# Sensor.net
KiCad netlist of a schematic drawn in Altium Designer
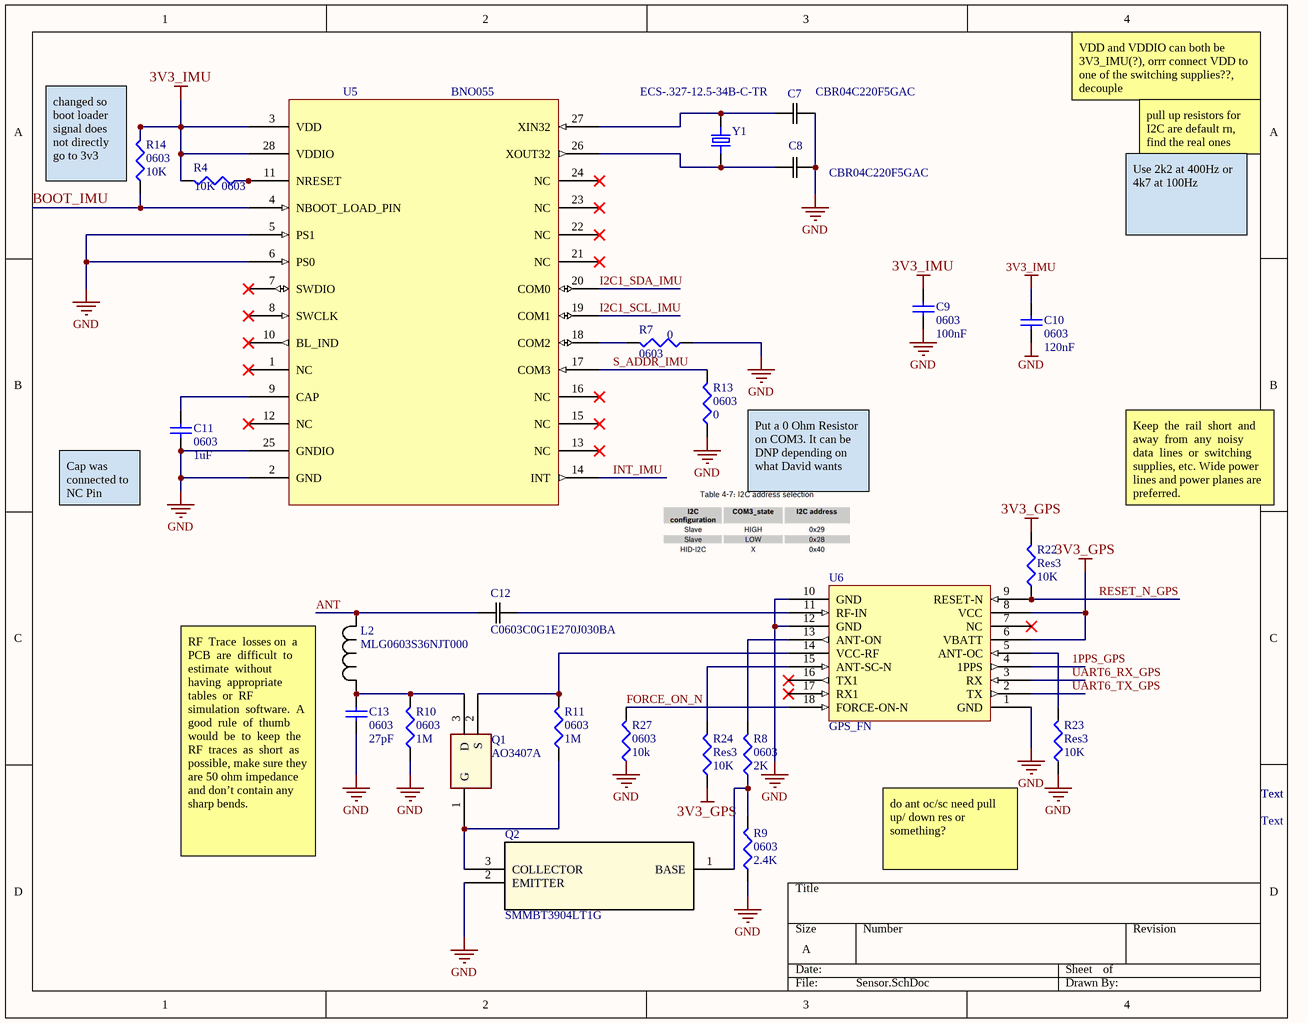
[diagram p0: Sensor.SchDoc]

(export (version "E")
  (design (tool "Eeschema 10.0.6"))
  (components
    (comp (ref "C7")
      (value "CBR04C220F5GAC")
      (footprint "swarm_crawler_pcb:CAPC10555_55N_KEM")
      (description "No Description Available")
      (fields (field (name "COPYRIGHT") "Copyright (C) 2023 Ultra Librarian. All rights reserved."))
      (libsource (lib "swarm_crawler_sch") (part "CBR04C220F5GAC"))
    )
    (comp (ref "C8")
      (value "CBR04C220F5GAC")
      (footprint "swarm_crawler_pcb:CAPC10555_55N_KEM")
      (description "No Description Available")
      (fields (field (name "COPYRIGHT") "Copyright (C) 2023 Ultra Librarian. All rights reserved."))
      (libsource (lib "swarm_crawler_sch") (part "CBR04C220F5GAC"))
    )
    (comp (ref "C9")
      (value "0603")
      (footprint "1608[0603]")
      (description "Capacitor (Semiconductor SIM Model)")
      (fields (field (name "ALTIUM_VALUE") "100nF") (field (name "PUBLISHER") "Altium Limited"))
      (libsource (lib "Miscellaneous Devices") (part "Cap Semi"))
    )
    (comp (ref "C10")
      (value "0603")
      (footprint "1608[0603]")
      (description "Capacitor (Semiconductor SIM Model)")
      (fields (field (name "ALTIUM_VALUE") "120nF") (field (name "PUBLISHER") "Altium Limited"))
      (libsource (lib "Miscellaneous Devices") (part "Cap Semi"))
    )
    (comp (ref "C11")
      (value "0603")
      (footprint "1608[0603]")
      (description "Capacitor (Semiconductor SIM Model)")
      (fields (field (name "ALTIUM_VALUE") "1uF") (field (name "PUBLISHER") "Altium Limited"))
      (libsource (lib "Miscellaneous Devices") (part "Cap Semi"))
    )
    (comp (ref "C12")
      (value "C0603C0G1E270J030BA")
      (footprint "swarm_crawler_pcb:CAP_0603_TDK")
      (description "No Description Available")
      (fields (field (name "COPYRIGHT") "Copyright (C) 2023 Ultra Librarian. All rights reserved."))
      (libsource (lib "swarm_crawler_sch") (part "C0603C0G1E270J030BA"))
    )
    (comp (ref "C13")
      (value "0603")
      (footprint "1608[0603]")
      (description "Capacitor (Semiconductor SIM Model)")
      (fields (field (name "ALTIUM_VALUE") "27pF") (field (name "PUBLISHER") "Altium Limited"))
      (libsource (lib "Miscellaneous Devices") (part "Cap Semi"))
    )
    (comp (ref "L2")
      (value "MLG0603S36NJT000")
      (footprint "swarm_crawler_pcb:IND_0603_TDK")
      (description "No Description Available")
      (fields (field (name "COPYRIGHT") "Copyright (C) 2023 Ultra Librarian. All rights reserved."))
      (libsource (lib "swarm_crawler_sch") (part "MLG0603S36NJT000"))
    )
    (comp (ref "Q1")
      (value "AO3407A")
      (footprint "swarm_crawler_pcb:SOT-23-3L_AOS")
      (description "No Description Available")
      (fields (field (name "COPYRIGHT") "Copyright (C) 2023 Ultra Librarian. All rights reserved."))
      (libsource (lib "swarm_crawler_sch") (part "AO3407A"))
    )
    (comp (ref "Q2")
      (value "SMMBT3904LT1G")
      (footprint "swarm_crawler_pcb:SOT-23-3_1P4X3P040_ONS")
      (description "No Description Available")
      (fields (field (name "COPYRIGHT") "Copyright (C) 2023 Ultra Librarian. All rights reserved."))
      (libsource (lib "swarm_crawler_sch") (part "SMMBT3904LT1G"))
    )
    (comp (ref "R4")
      (value "0603")
      (footprint "J1-0603")
      (description "Resistor")
      (fields (field (name "ALTIUM_VALUE") "10K") (field (name "PUBLISHER") "Altium Limited"))
      (libsource (lib "Miscellaneous Devices") (part "Res3"))
    )
    (comp (ref "R7")
      (value "0603")
      (footprint "J1-0603")
      (description "Resistor")
      (fields (field (name "ALTIUM_VALUE") "0") (field (name "PUBLISHER") "Altium Limited"))
      (libsource (lib "Miscellaneous Devices") (part "Res3"))
    )
    (comp (ref "R8")
      (value "0603")
      (footprint "J1-0603")
      (description "Resistor")
      (fields (field (name "ALTIUM_VALUE") "2K") (field (name "PUBLISHER") "Altium Limited"))
      (libsource (lib "Miscellaneous Devices") (part "Res3"))
    )
    (comp (ref "R9")
      (value "0603")
      (footprint "J1-0603")
      (description "Resistor")
      (fields (field (name "ALTIUM_VALUE") "2.4K") (field (name "PUBLISHER") "Altium Limited"))
      (libsource (lib "Miscellaneous Devices") (part "Res3"))
    )
    (comp (ref "R10")
      (value "0603")
      (footprint "J1-0603")
      (description "Resistor")
      (fields (field (name "ALTIUM_VALUE") "1M") (field (name "PUBLISHER") "Altium Limited"))
      (libsource (lib "Miscellaneous Devices") (part "Res3"))
    )
    (comp (ref "R11")
      (value "0603")
      (footprint "J1-0603")
      (description "Resistor")
      (fields (field (name "ALTIUM_VALUE") "1M") (field (name "PUBLISHER") "Altium Limited"))
      (libsource (lib "Miscellaneous Devices") (part "Res3"))
    )
    (comp (ref "R13")
      (value "0603")
      (footprint "J1-0603")
      (description "Resistor")
      (fields (field (name "ALTIUM_VALUE") "0") (field (name "PUBLISHER") "Altium Limited"))
      (libsource (lib "Miscellaneous Devices") (part "Res3"))
    )
    (comp (ref "R14")
      (value "0603")
      (footprint "J1-0603")
      (description "Resistor")
      (fields (field (name "ALTIUM_VALUE") "10K") (field (name "PUBLISHER") "Altium Limited"))
      (libsource (lib "Miscellaneous Devices") (part "Res3"))
    )
    (comp (ref "R22")
      (value "Res3")
      (footprint "J1-0603")
      (description "Resistor")
      (fields (field (name "ALTIUM_VALUE") "10K") (field (name "PUBLISHER") "Altium Limited"))
      (libsource (lib "Miscellaneous Devices") (part "Res3"))
    )
    (comp (ref "R23")
      (value "Res3")
      (footprint "J1-0603")
      (description "Resistor")
      (fields (field (name "ALTIUM_VALUE") "10K") (field (name "PUBLISHER") "Altium Limited"))
      (libsource (lib "Miscellaneous Devices") (part "Res3"))
    )
    (comp (ref "R24")
      (value "Res3")
      (footprint "J1-0603")
      (description "Resistor")
      (fields (field (name "ALTIUM_VALUE") "10K") (field (name "PUBLISHER") "Altium Limited"))
      (libsource (lib "Miscellaneous Devices") (part "Res3"))
    )
    (comp (ref "R27")
      (value "0603")
      (footprint "J1-0603")
      (description "Resistor")
      (fields (field (name "ALTIUM_VALUE") "10k") (field (name "PUBLISHER") "Altium Limited"))
      (libsource (lib "Miscellaneous Devices") (part "Res3"))
    )
    (comp (ref "U5")
      (value "BNO055")
      (footprint "swarm_crawler_pcb:QFN_BNO055_BOS")
      (description "No Description Available")
      (fields (field (name "COPYRIGHT") "Copyright (C) 2023 Ultra Librarian. All rights reserved."))
      (libsource (lib "swarm_crawler_sch") (part "BNO055"))
    )
    (comp (ref "U6")
      (value "GPS_FN")
      (footprint "swarm_crawler_pcb:SL871")
      (libsource (lib "swarm_crawler_sch") (part "GPS_FN"))
    )
    (comp (ref "Y1")
      (value "ECS-.327-12.5-34B-C-TR")
      (footprint "swarm_crawler_pcb:XTAL_ECS-.327-12.5-34B-C-TR")
      (description "32.768kHz Â±10ppm Crystal 12.5pF 70 kOhms 2-SMD, No Lead")
      (fields (field (name "DIGI-KEY_PART_NUMBER") "XC1968CT-ND") (field (name "MF") "ECS Inc."))
      (libsource (lib "swarm_crawler_sch") (part "ECS-.327-12.5-34B-C-TR"))
    )
  )
  (nets
    (net (code "1") (name "/1PPS_GPS") (class "Default")
      (node (ref "U6") (pin "4") (pinfunction "1PPS_4") (pintype "output"))
    )
    (net (code "2") (name "/ANT") (class "Default")
      (node (ref "C12") (pin "1") (pinfunction "1_1") (pintype "passive"))
      (node (ref "L2") (pin "1") (pinfunction "1_1") (pintype "passive"))
    )
    (net (code "3") (name "/BOOT_IMU") (class "Default")
      (node (ref "R14") (pin "1") (pinfunction "1_1") (pintype "passive"))
      (node (ref "U5") (pin "4") (pinfunction "NBOOT_LOAD_PIN_4") (pintype "input"))
    )
    (net (code "4") (name "/FORCE_ON_N") (class "Default")
      (node (ref "R27") (pin "2") (pinfunction "2_2") (pintype "passive"))
      (node (ref "U6") (pin "18") (pinfunction "FORCE-ON-N_18") (pintype "input"))
    )
    (net (code "5") (name "/I2C1_SCL_IMU") (class "Default")
      (node (ref "U5") (pin "19") (pinfunction "COM1_19") (pintype "bidirectional"))
    )
    (net (code "6") (name "/I2C1_SDA_IMU") (class "Default")
      (node (ref "U5") (pin "20") (pinfunction "COM0_20") (pintype "bidirectional"))
    )
    (net (code "7") (name "/INT_IMU") (class "Default")
      (node (ref "U5") (pin "14") (pinfunction "INT_14") (pintype "output"))
    )
    (net (code "8") (name "/RESET_N_GPS") (class "Default")
      (node (ref "R22") (pin "1") (pinfunction "1_1") (pintype "passive"))
      (node (ref "U6") (pin "9") (pinfunction "RESET-N_9") (pintype "input"))
    )
    (net (code "9") (name "/S_ADDR_IMU") (class "Default")
      (node (ref "R13") (pin "2") (pinfunction "2_2") (pintype "passive"))
      (node (ref "U5") (pin "17") (pinfunction "COM3_17") (pintype "input"))
    )
    (net (code "10") (name "/UART6_RX_GPS") (class "Default")
      (node (ref "U6") (pin "3") (pinfunction "RX_3") (pintype "input"))
    )
    (net (code "11") (name "/UART6_TX_GPS") (class "Default")
      (node (ref "U6") (pin "2") (pinfunction "TX_2") (pintype "output"))
    )
    (net (code "12") (name "3V3_GPS") (class "Default")
      (node (ref "R22") (pin "2") (pinfunction "2_2") (pintype "passive"))
      (node (ref "R24") (pin "1") (pinfunction "1_1") (pintype "passive"))
      (node (ref "U6") (pin "6") (pinfunction "VBATT_6") (pintype "power_in"))
      (node (ref "U6") (pin "8") (pinfunction "VCC_8") (pintype "power_in"))
    )
    (net (code "13") (name "3V3_IMU") (class "Default")
      (node (ref "C10") (pin "2") (pinfunction "2_2") (pintype "passive"))
      (node (ref "C9") (pin "2") (pinfunction "2_2") (pintype "passive"))
      (node (ref "R14") (pin "2") (pinfunction "2_2") (pintype "passive"))
      (node (ref "R4") (pin "2") (pinfunction "2_2") (pintype "passive"))
      (node (ref "U5") (pin "28") (pinfunction "VDDIO_28") (pintype "power_in"))
      (node (ref "U5") (pin "3") (pinfunction "VDD_3") (pintype "power_in"))
    )
    (net (code "14") (name "GND") (class "Default")
      (node (ref "C10") (pin "1") (pinfunction "1_1") (pintype "passive"))
      (node (ref "C11") (pin "1") (pinfunction "1_1") (pintype "passive"))
      (node (ref "C13") (pin "1") (pinfunction "1_1") (pintype "passive"))
      (node (ref "C7") (pin "2") (pinfunction "2_2") (pintype "passive"))
      (node (ref "C8") (pin "2") (pinfunction "2_2") (pintype "passive"))
      (node (ref "C9") (pin "1") (pinfunction "1_1") (pintype "passive"))
      (node (ref "Q2") (pin "2") (pinfunction "EMITTER_2") (pintype "passive"))
      (node (ref "R10") (pin "1") (pinfunction "1_1") (pintype "passive"))
      (node (ref "R13") (pin "1") (pinfunction "1_1") (pintype "passive"))
      (node (ref "R23") (pin "1") (pinfunction "1_1") (pintype "passive"))
      (node (ref "R7") (pin "1") (pinfunction "1_1") (pintype "passive"))
      (node (ref "R9") (pin "1") (pinfunction "1_1") (pintype "passive"))
      (node (ref "U5") (pin "2") (pinfunction "GND_2") (pintype "passive"))
      (node (ref "U5") (pin "25") (pinfunction "GNDIO_25") (pintype "passive"))
      (node (ref "U5") (pin "5") (pinfunction "PS1_5") (pintype "input"))
      (node (ref "U5") (pin "6") (pinfunction "PS0_6") (pintype "input"))
      (node (ref "U6") (pin "1") (pinfunction "GND_1") (pintype "power_in"))
      (node (ref "U6") (pin "10") (pinfunction "GND_10") (pintype "power_in"))
      (node (ref "U6") (pin "12") (pinfunction "GND_12") (pintype "power_in"))
    )
    (net (code "15") (name "Net-(Q1-D)") (class "Default")
      (node (ref "C13") (pin "2") (pinfunction "2_2") (pintype "passive"))
      (node (ref "L2") (pin "2") (pinfunction "2_2") (pintype "passive"))
      (node (ref "Q1") (pin "3") (pinfunction "D_3") (pintype "passive"))
      (node (ref "R10") (pin "2") (pinfunction "2_2") (pintype "passive"))
    )
    (net (code "16") (name "Net-(Q1-G)") (class "Default")
      (node (ref "Q1") (pin "1") (pinfunction "G_1") (pintype "passive"))
      (node (ref "Q2") (pin "3") (pinfunction "COLLECTOR_3") (pintype "passive"))
      (node (ref "R11") (pin "1") (pinfunction "1_1") (pintype "passive"))
    )
    (net (code "17") (name "Net-(Q1-S)") (class "Default")
      (node (ref "Q1") (pin "2") (pinfunction "S_2") (pintype "passive"))
      (node (ref "R11") (pin "2") (pinfunction "2_2") (pintype "passive"))
      (node (ref "U6") (pin "14") (pinfunction "VCC-RF_14") (pintype "power_in"))
    )
    (net (code "18") (name "Net-(Q2-BASE)") (class "Default")
      (node (ref "Q2") (pin "1") (pinfunction "BASE_1") (pintype "passive"))
      (node (ref "R8") (pin "1") (pinfunction "1_1") (pintype "passive"))
      (node (ref "R9") (pin "2") (pinfunction "2_2") (pintype "passive"))
    )
    (net (code "19") (name "Net-(U5-CAP)") (class "Default")
      (node (ref "C11") (pin "2") (pinfunction "2_2") (pintype "passive"))
      (node (ref "U5") (pin "9") (pinfunction "CAP_9") (pintype "passive"))
    )
    (net (code "20") (name "Net-(U5-COM2)") (class "Default")
      (node (ref "R7") (pin "2") (pinfunction "2_2") (pintype "passive"))
      (node (ref "U5") (pin "18") (pinfunction "COM2_18") (pintype "bidirectional"))
    )
    (net (code "21") (name "Net-(U5-NRESET)") (class "Default")
      (node (ref "R4") (pin "1") (pinfunction "1_1") (pintype "passive"))
      (node (ref "U5") (pin "11") (pinfunction "NRESET_11") (pintype "passive"))
    )
    (net (code "22") (name "Net-(U5-XIN32)") (class "Default")
      (node (ref "C7") (pin "1") (pinfunction "1_1") (pintype "passive"))
      (node (ref "U5") (pin "27") (pinfunction "XIN32_27") (pintype "input"))
      (node (ref "Y1") (pin "2") (pinfunction "2_2") (pintype "passive"))
    )
    (net (code "23") (name "Net-(U5-XOUT32)") (class "Default")
      (node (ref "C8") (pin "1") (pinfunction "1_1") (pintype "passive"))
      (node (ref "U5") (pin "26") (pinfunction "XOUT32_26") (pintype "output"))
      (node (ref "Y1") (pin "1") (pinfunction "1_1") (pintype "passive"))
    )
    (net (code "24") (name "Net-(U6-ANT-OC)") (class "Default")
      (node (ref "R23") (pin "2") (pinfunction "2_2") (pintype "passive"))
      (node (ref "U6") (pin "5") (pinfunction "ANT-OC_5") (pintype "input"))
    )
    (net (code "25") (name "Net-(U6-ANT-ON)") (class "Default")
      (node (ref "R8") (pin "2") (pinfunction "2_2") (pintype "passive"))
      (node (ref "U6") (pin "13") (pinfunction "ANT-ON_13") (pintype "output"))
    )
    (net (code "26") (name "Net-(U6-ANT-SC-N)") (class "Default")
      (node (ref "R24") (pin "2") (pinfunction "2_2") (pintype "passive"))
      (node (ref "U6") (pin "15") (pinfunction "ANT-SC-N_15") (pintype "input"))
    )
    (net (code "27") (name "Net-(U6-RF-IN)") (class "Default")
      (node (ref "C12") (pin "2") (pinfunction "2_2") (pintype "passive"))
      (node (ref "U6") (pin "11") (pinfunction "RF-IN_11") (pintype "input"))
    )
    (net (code "28") (name "unconnected-(R27-Pad1)") (class "Default")
      (node (ref "R27") (pin "1") (pinfunction "1_1") (pintype "passive"))
    )
    (net (code "29") (name "unconnected-(U5-BL_IND-Pad10)") (class "Default")
      (node (ref "U5") (pin "10") (pinfunction "BL_IND_10") (pintype "output+no_connect"))
    )
    (net (code "30") (name "unconnected-(U5-NC-Pad1)") (class "Default")
      (node (ref "U5") (pin "1") (pinfunction "NC_1") (pintype "passive+no_connect"))
    )
    (net (code "31") (name "unconnected-(U5-NC-Pad12)") (class "Default")
      (node (ref "U5") (pin "12") (pinfunction "NC_12") (pintype "passive+no_connect"))
    )
    (net (code "32") (name "unconnected-(U5-NC-Pad13)") (class "Default")
      (node (ref "U5") (pin "13") (pinfunction "NC_13") (pintype "passive+no_connect"))
    )
    (net (code "33") (name "unconnected-(U5-NC-Pad15)") (class "Default")
      (node (ref "U5") (pin "15") (pinfunction "NC_15") (pintype "passive+no_connect"))
    )
    (net (code "34") (name "unconnected-(U5-NC-Pad16)") (class "Default")
      (node (ref "U5") (pin "16") (pinfunction "NC_16") (pintype "passive+no_connect"))
    )
    (net (code "35") (name "unconnected-(U5-NC-Pad21)") (class "Default")
      (node (ref "U5") (pin "21") (pinfunction "NC_21") (pintype "passive+no_connect"))
    )
    (net (code "36") (name "unconnected-(U5-NC-Pad22)") (class "Default")
      (node (ref "U5") (pin "22") (pinfunction "NC_22") (pintype "passive+no_connect"))
    )
    (net (code "37") (name "unconnected-(U5-NC-Pad23)") (class "Default")
      (node (ref "U5") (pin "23") (pinfunction "NC_23") (pintype "passive+no_connect"))
    )
    (net (code "38") (name "unconnected-(U5-NC-Pad24)") (class "Default")
      (node (ref "U5") (pin "24") (pinfunction "NC_24") (pintype "passive+no_connect"))
    )
    (net (code "39") (name "unconnected-(U5-SWCLK-Pad8)") (class "Default")
      (node (ref "U5") (pin "8") (pinfunction "SWCLK_8") (pintype "input+no_connect"))
    )
    (net (code "40") (name "unconnected-(U5-SWDIO-Pad7)") (class "Default")
      (node (ref "U5") (pin "7") (pinfunction "SWDIO_7") (pintype "bidirectional+no_connect"))
    )
    (net (code "41") (name "unconnected-(U6-NC-Pad7)") (class "Default")
      (node (ref "U6") (pin "7") (pinfunction "NC_7") (pintype "passive+no_connect"))
    )
    (net (code "42") (name "unconnected-(U6-RX1-Pad17)") (class "Default")
      (node (ref "U6") (pin "17") (pinfunction "RX1_17") (pintype "input+no_connect"))
    )
    (net (code "43") (name "unconnected-(U6-TX1-Pad16)") (class "Default")
      (node (ref "U6") (pin "16") (pinfunction "TX1_16") (pintype "output+no_connect"))
    )
  )
)
